# Power_Generation_-_Buck_Converter.net
KiCad netlist of a schematic drawn in Altium Designer
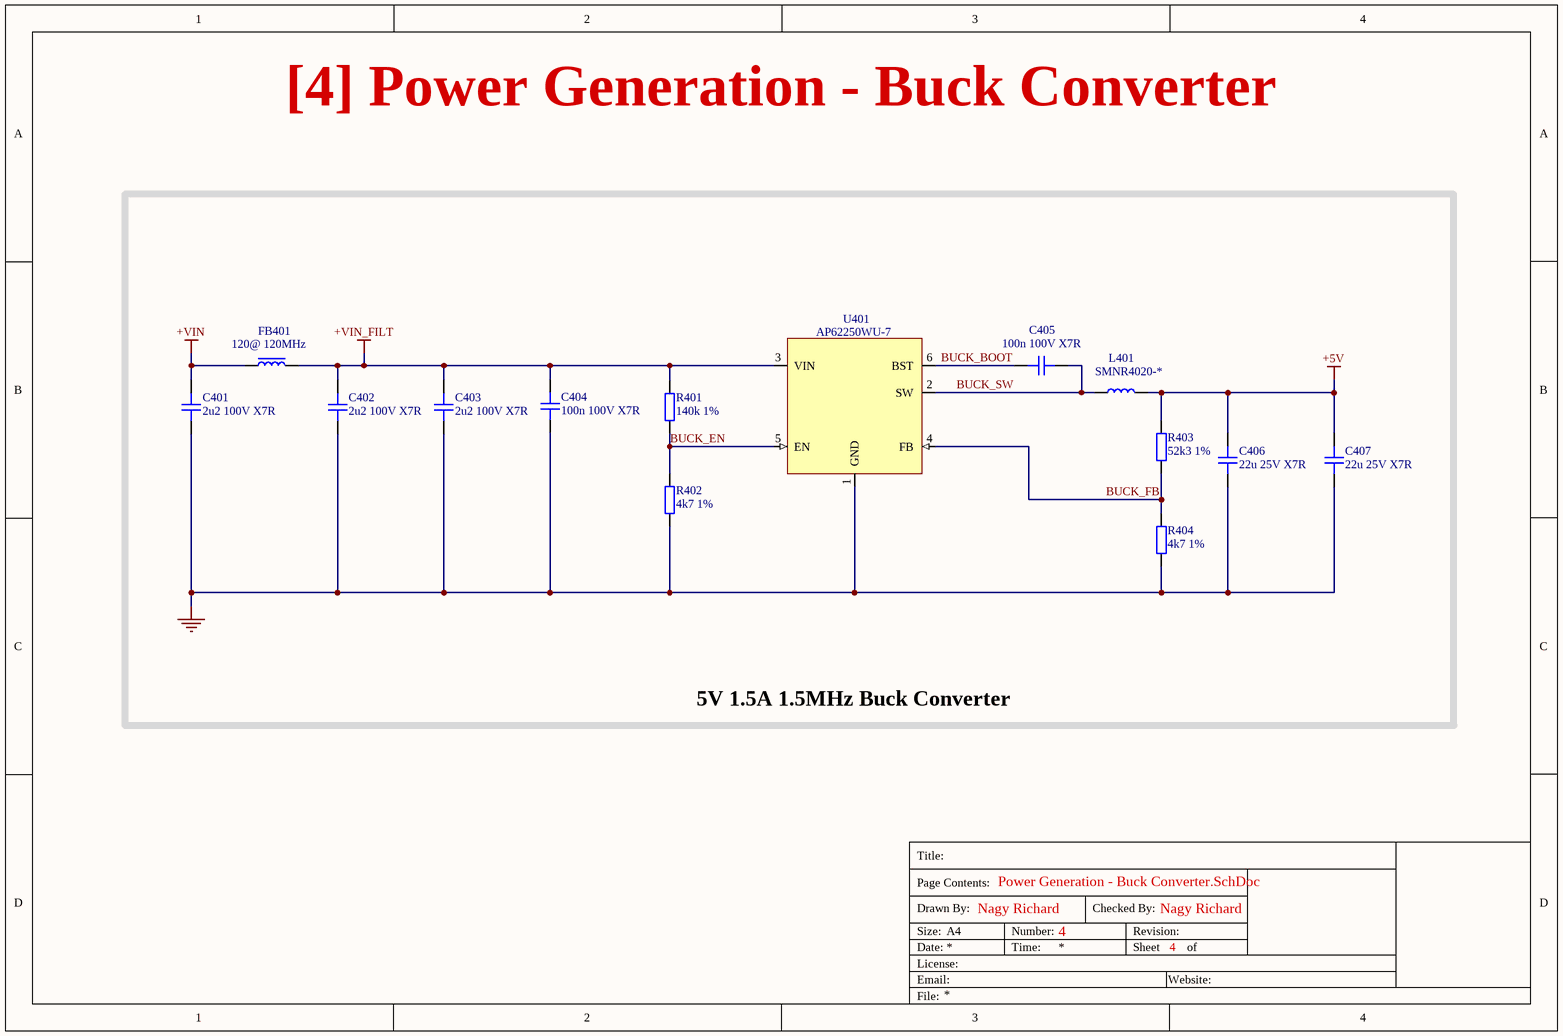
[diagram p0: Power Generation - Buck Converter.SchDoc]

(export (version "E")
  (design (tool "Eeschema 10.0.6"))
  (components
    (comp (ref "C401")
      (value "2u2 100V X7R")
      (footprint "CAP_0805")
      (description "Capacitor SMD 0805")
      (libsource (lib "Schematic-Lib") (part "CAP_0805"))
    )
    (comp (ref "C402")
      (value "2u2 100V X7R")
      (footprint "CAP_0805")
      (description "Capacitor SMD 0805")
      (libsource (lib "Schematic-Lib") (part "CAP_0805"))
    )
    (comp (ref "C403")
      (value "2u2 100V X7R")
      (footprint "CAP_0805")
      (description "Capacitor SMD 0805")
      (libsource (lib "Schematic-Lib") (part "CAP_0805"))
    )
    (comp (ref "C404")
      (value "100n 100V X7R")
      (footprint "CAP_0805")
      (description "Capacitor SMD 0805")
      (fields
        (field (name "MANUFACTURER") "HUI JU")
        (field (name "MANUFACTURER PART NUMBER") "NM0805B104K101CEDN")
      )
      (libsource (lib "Schematic-Lib-PhilsLab") (part "CAP_0805"))
    )
    (comp (ref "C405")
      (value "100n 100V X7R")
      (footprint "CAP_0805")
      (description "Capacitor SMD 0805")
      (fields
        (field (name "MANUFACTURER") "HUI JU")
        (field (name "MANUFACTURER PART NUMBER") "NM0805B104K101CEDN")
      )
      (libsource (lib "Schematic-Lib-PhilsLab") (part "CAP_0805"))
    )
    (comp (ref "C406")
      (value "22u 25V X7R")
      (footprint "CAP_0805")
      (description "Capacitor SMD 0805")
      (libsource (lib "Schematic-Lib") (part "CAP_0805"))
    )
    (comp (ref "C407")
      (value "22u 25V X7R")
      (footprint "CAP_0805")
      (description "Capacitor SMD 0805")
      (libsource (lib "Schematic-Lib") (part "CAP_0805"))
    )
    (comp (ref "FB401")
      (value "120@ 120MHz")
      (footprint "FB_0805")
      (description "Ferrite Bead SMD 0805")
      (fields
        (field (name "MANUFACTURER") "Murata Electronics")
        (field (name "MANUFACTURER PART NUMBER") "BLM21AG121SN1D")
      )
      (libsource (lib "Schematic-Lib-PhilsLab") (part "FB_0805"))
    )
    (comp (ref "L401")
      (value "SMNR4020-*")
      (footprint "SMNR4020")
      (description "Inductor SXN SMNR4020 Series 4x4x2mm")
      (fields (field (name "MANUFACTURER") "SXN") (field (name "MANUFACTURER PART NUMBER") "SMNR4020-5R6MT"))
      (libsource (lib "Schematic-Lib") (part "SMNR4020-*"))
    )
    (comp (ref "R401")
      (value "140k 1%")
      (footprint "RES_0603")
      (description "Resistor SMD 0603")
      (fields
        (field (name "MANUFACTURER") "YAGEO")
        (field (name "MANUFACTURER PART NUMBER") "RC0603FR-07140KL")
      )
      (libsource (lib "Schematic-Lib-PhilsLab") (part "RES_0603"))
    )
    (comp (ref "R402")
      (value "4k7 1%")
      (footprint "RES_0603")
      (description "Resistor SMD 0603")
      (fields
        (field (name "MANUFACTURER") "UNI-ROYAL(Uniroyal Elec)")
        (field (name "MANUFACTURER PART NUMBER") "0603WAF4701T5E")
      )
      (libsource (lib "Schematic-Lib-PhilsLab") (part "RES_0603"))
    )
    (comp (ref "R403")
      (value "52k3 1%")
      (footprint "RES_0603")
      (description "Resistor SMD 0603")
      (fields
        (field (name "MANUFACTURER") "UNI-ROYAL(Uniroyal Elec)")
        (field (name "MANUFACTURER PART NUMBER") "0603WAF5232T5E")
      )
      (libsource (lib "Schematic-Lib-PhilsLab") (part "RES_0603"))
    )
    (comp (ref "R404")
      (value "4k7 1%")
      (footprint "RES_0603")
      (description "Resistor SMD 0603")
      (fields
        (field (name "MANUFACTURER") "UNI-ROYAL(Uniroyal Elec)")
        (field (name "MANUFACTURER PART NUMBER") "0603WAF4701T5E")
      )
      (libsource (lib "Schematic-Lib-PhilsLab") (part "RES_0603"))
    )
    (comp (ref "U401")
      (value "AP62250WU-7")
      (footprint "TSOT-26-6")
      (description "4.2V TO 18V INPUT, 2.5A LOW IQ SYNCHRONOUS BUCK CONVERTER")
      (fields (field (name "MANUFACTURER") "Diodes Incorporated"))
      (libsource (lib "Schematic-Lib") (part "AP62250WU-7"))
    )
  )
  (nets
    (net (code "1") (name "+5V") (class "Default")
      (node (ref "C406") (pin "2") (pinfunction "2_2") (pintype "passive"))
      (node (ref "C407") (pin "2") (pinfunction "2_2") (pintype "passive"))
      (node (ref "L401") (pin "2") (pinfunction "2_2") (pintype "passive"))
      (node (ref "R403") (pin "2") (pinfunction "2_2") (pintype "passive"))
    )
    (net (code "2") (name "+VIN") (class "Default")
      (node (ref "C401") (pin "2") (pinfunction "2_2") (pintype "passive"))
      (node (ref "FB401") (pin "1") (pinfunction "1_1") (pintype "passive"))
    )
    (net (code "3") (name "+VIN_FILT") (class "Default")
      (node (ref "C402") (pin "2") (pinfunction "2_2") (pintype "passive"))
      (node (ref "C403") (pin "2") (pinfunction "2_2") (pintype "passive"))
      (node (ref "C404") (pin "2") (pinfunction "2_2") (pintype "passive"))
      (node (ref "FB401") (pin "2") (pinfunction "2_2") (pintype "passive"))
      (node (ref "R401") (pin "2") (pinfunction "2_2") (pintype "passive"))
      (node (ref "U401") (pin "3") (pinfunction "VIN_3") (pintype "power_in"))
    )
    (net (code "4") (name "/BUCK_BOOT") (class "Default")
      (node (ref "C405") (pin "2") (pinfunction "2_2") (pintype "passive"))
      (node (ref "U401") (pin "6") (pinfunction "BST_6") (pintype "power_in"))
    )
    (net (code "5") (name "/BUCK_EN") (class "Default")
      (node (ref "R401") (pin "1") (pinfunction "1_1") (pintype "passive"))
      (node (ref "R402") (pin "2") (pinfunction "2_2") (pintype "passive"))
      (node (ref "U401") (pin "5") (pinfunction "EN_5") (pintype "input"))
    )
    (net (code "6") (name "/BUCK_FB") (class "Default")
      (node (ref "R403") (pin "1") (pinfunction "1_1") (pintype "passive"))
      (node (ref "R404") (pin "2") (pinfunction "2_2") (pintype "passive"))
      (node (ref "U401") (pin "4") (pinfunction "FB_4") (pintype "input"))
    )
    (net (code "7") (name "/BUCK_SW") (class "Default")
      (node (ref "C405") (pin "1") (pinfunction "1_1") (pintype "passive"))
      (node (ref "L401") (pin "1") (pinfunction "1_1") (pintype "passive"))
      (node (ref "U401") (pin "2") (pinfunction "SW_2") (pintype "power_in"))
    )
    (net (code "8") (name "GND") (class "Default")
      (node (ref "C401") (pin "1") (pinfunction "1_1") (pintype "passive"))
      (node (ref "C402") (pin "1") (pinfunction "1_1") (pintype "passive"))
      (node (ref "C403") (pin "1") (pinfunction "1_1") (pintype "passive"))
      (node (ref "C404") (pin "1") (pinfunction "1_1") (pintype "passive"))
      (node (ref "C406") (pin "1") (pinfunction "1_1") (pintype "passive"))
      (node (ref "C407") (pin "1") (pinfunction "1_1") (pintype "passive"))
      (node (ref "R402") (pin "1") (pinfunction "1_1") (pintype "passive"))
      (node (ref "R404") (pin "1") (pinfunction "1_1") (pintype "passive"))
      (node (ref "U401") (pin "1") (pinfunction "GND_1") (pintype "power_in"))
    )
  )
)
